# power.net
KiCad netlist of a schematic drawn in Altium Designer
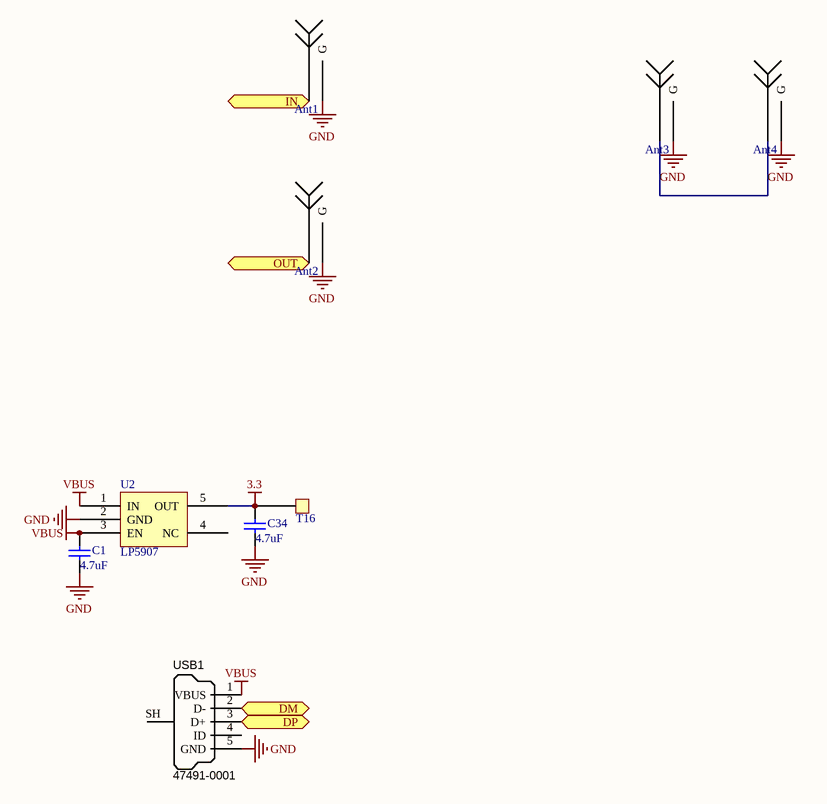
[diagram p0: power.SchDoc]

(export (version "E")
  (design (tool "Eeschema 10.0.6"))
  (components
    (comp (ref "Ant1")
      (value "Antenna")
      (footprint "BK5811:SMA-2")
      (libsource (lib "RTC6705") (part "Antenna"))
    )
    (comp (ref "Ant2")
      (value "Antenna")
      (footprint "BK5811:SMA-2")
      (libsource (lib "RTC6705") (part "Antenna"))
    )
    (comp (ref "Ant3")
      (value "Antenna")
      (footprint "BK5811:SMA-2")
      (libsource (lib "RTC6705") (part "Antenna"))
    )
    (comp (ref "Ant4")
      (value "Antenna")
      (footprint "BK5811:SMA-2")
      (libsource (lib "RTC6705") (part "Antenna"))
    )
    (comp (ref "C1")
      (value "4.7uF")
      (footprint "0603")
      (description "Capacitor")
      (fields (field (name "PUBLISHER") "Altium Limited"))
      (libsource (lib "RTC6705") (part "Cap"))
    )
    (comp (ref "C34")
      (value "4.7uF")
      (footprint "0603")
      (description "Capacitor")
      (fields (field (name "PUBLISHER") "Altium Limited"))
      (libsource (lib "RTC6705") (part "Cap"))
    )
    (comp (ref "T16") (value "TestPad") (footprint "TestPad - 1mm") (libsource (lib "sch") (part "TestPad")))
    (comp (ref "U2") (value "LP5907") (footprint "SOT23-5") (libsource (lib "RTC6705") (part "LP5907")))
    (comp (ref "USB1")
      (value "USB Micro Type B")
      (footprint "MICRO-YZX")
      (description "Connector SMD USB Micro Type B middle mount")
      (fields (field (name "MANUFACTURER PART NUMBER 1") "47491-0001"))
      (libsource (lib "PBL - Connectors") (part "USB_Micro_TypeB"))
    )
  )
  (nets
    (net (code "1") (name "/DM") (class "Default")
      (node (ref "USB1") (pin "2") (pinfunction "D-_2") (pintype "passive"))
    )
    (net (code "2") (name "/DP") (class "Default")
      (node (ref "USB1") (pin "3") (pinfunction "D+_3") (pintype "passive"))
    )
    (net (code "3") (name "/IN") (class "Default")
      (node (ref "Ant1") (pin "1") (pinfunction "1_1") (pintype "passive"))
    )
    (net (code "4") (name "/OUT") (class "Default")
      (node (ref "Ant2") (pin "1") (pinfunction "1_1") (pintype "passive"))
    )
    (net (code "5") (name "3.3") (class "Default")
      (node (ref "C34") (pin "2") (pinfunction "2_2") (pintype "passive"))
      (node (ref "T16") (pin "1") (pinfunction "3_1") (pintype "passive"))
      (node (ref "U2") (pin "5") (pinfunction "OUT_5") (pintype "passive"))
    )
    (net (code "6") (name "GND") (class "Default")
      (node (ref "Ant1") (pin "GND") (pinfunction "G_GND") (pintype "passive"))
      (node (ref "Ant2") (pin "GND") (pinfunction "G_GND") (pintype "passive"))
      (node (ref "Ant3") (pin "GND") (pinfunction "G_GND") (pintype "passive"))
      (node (ref "Ant4") (pin "GND") (pinfunction "G_GND") (pintype "passive"))
      (node (ref "C1") (pin "1") (pinfunction "1_1") (pintype "passive"))
      (node (ref "C34") (pin "1") (pinfunction "1_1") (pintype "passive"))
      (node (ref "U2") (pin "2") (pinfunction "GND_2") (pintype "passive"))
      (node (ref "USB1") (pin "5") (pinfunction "GND_5") (pintype "passive"))
    )
    (net (code "7") (name "Net-(Ant3-Pad1)") (class "Default")
      (node (ref "Ant3") (pin "1") (pinfunction "1_1") (pintype "passive"))
      (node (ref "Ant4") (pin "1") (pinfunction "1_1") (pintype "passive"))
    )
    (net (code "8") (name "VBUS") (class "Default")
      (node (ref "C1") (pin "2") (pinfunction "2_2") (pintype "passive"))
      (node (ref "U2") (pin "1") (pinfunction "IN_1") (pintype "passive"))
      (node (ref "U2") (pin "3") (pinfunction "EN_3") (pintype "passive"))
      (node (ref "USB1") (pin "1") (pinfunction "VBUS_1") (pintype "passive"))
    )
    (net (code "9") (name "unconnected-(U2-NC-Pad4)") (class "Default")
      (node (ref "U2") (pin "4") (pinfunction "NC_4") (pintype "passive"))
    )
    (net (code "10") (name "unconnected-(USB1-ID-Pad4)") (class "Default")
      (node (ref "USB1") (pin "4") (pinfunction "ID_4") (pintype "passive"))
    )
    (net (code "11") (name "unconnected-(USB1-Shell-PadSH)") (class "Default")
      (node (ref "USB1") (pin "SH") (pinfunction "Shell_SH") (pintype "passive"))
    )
  )
)
